# 01.net
KiCad netlist of a schematic drawn in EasyEDA
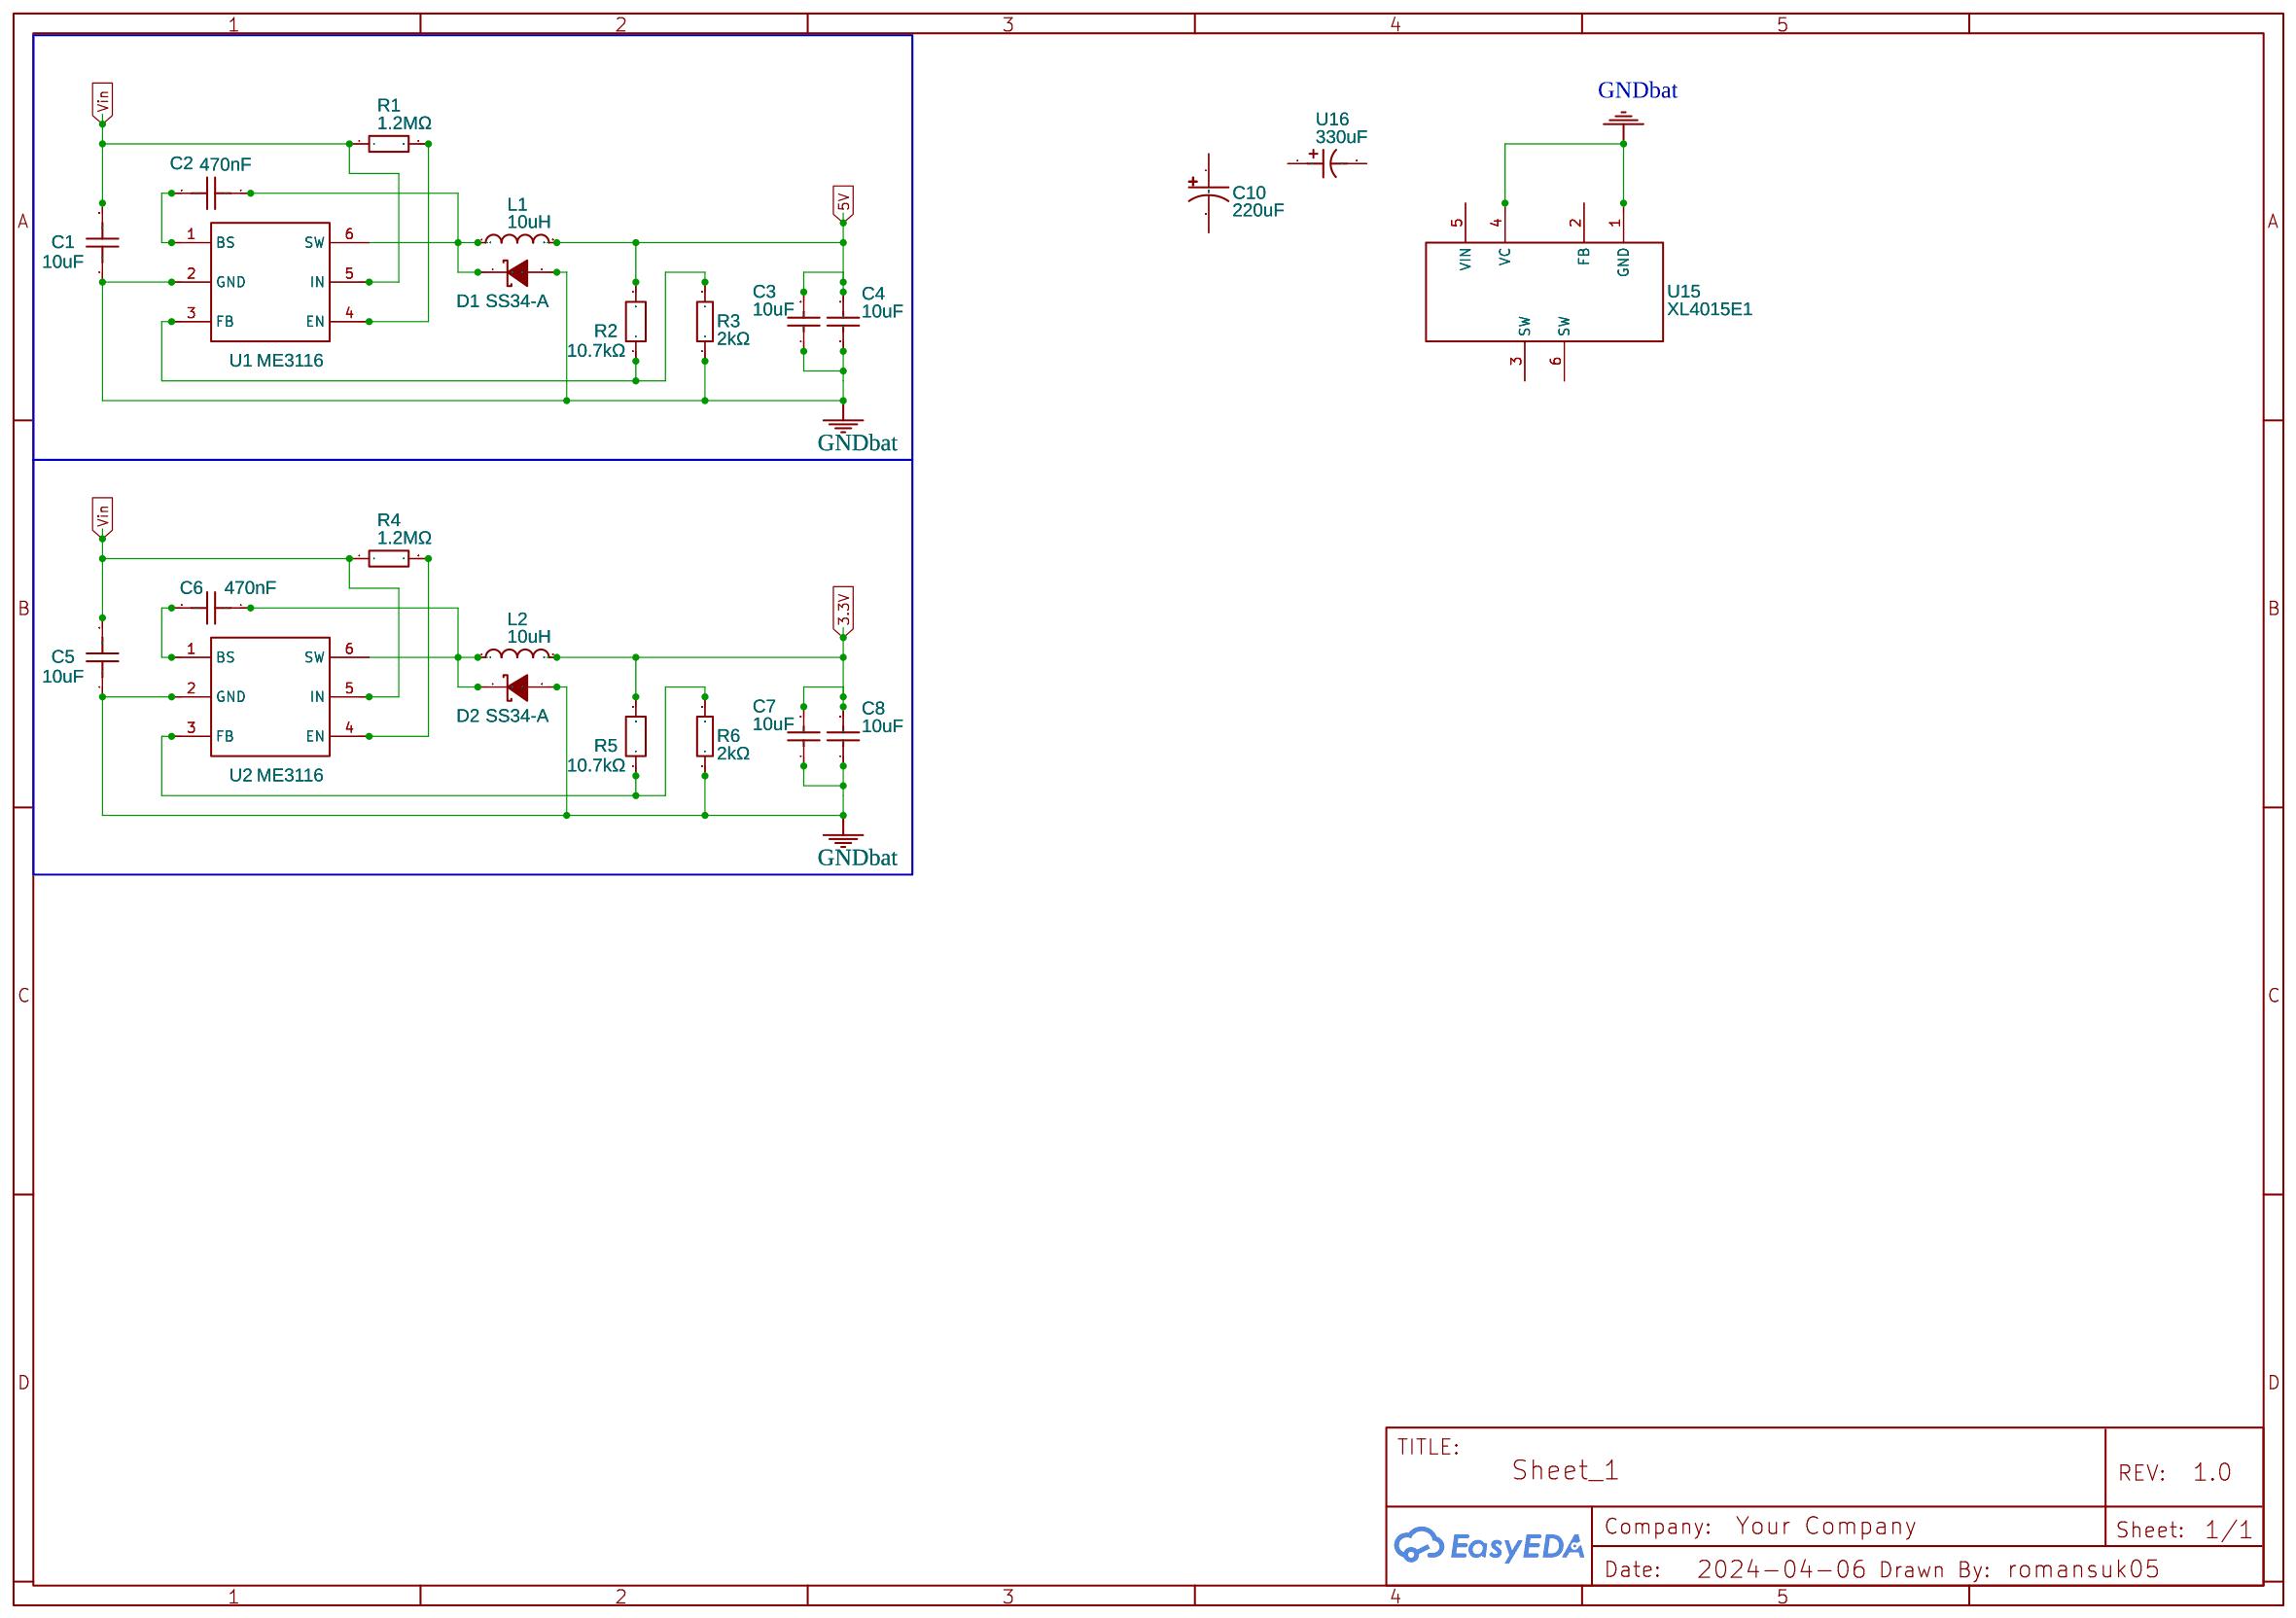
[diagram p0: schematic sheet]

(export (version "E")
  (design (tool "Eeschema 10.0.6"))
  (components
    (comp (ref "C1")
      (value "10uF")
      (fields
        (field (name "Manufacturer Part") "TCC1206X7R106K250HT")
        (field (name "Manufacturer") "CCTC(三环)")
      )
      (libsource (lib "") (part "TCC1206X7R106K250HT"))
    )
    (comp (ref "C2")
      (value "470nF")
      (fields
        (field (name "Manufacturer Part") "TCC1206X7R474K500FT")
        (field (name "Manufacturer") "CCTC(三环)")
      )
      (libsource (lib "") (part "TCC1206X7R474K500FT"))
    )
    (comp (ref "C3")
      (value "10uF")
      (fields
        (field (name "Manufacturer Part") "TMK316B7106KL-TD")
        (field (name "Manufacturer") "TAIYO YUDEN(太诱)")
      )
      (libsource (lib "") (part "TMK316B7106KL-TD"))
    )
    (comp (ref "C4")
      (value "10uF")
      (fields
        (field (name "Manufacturer Part") "TMK316B7106KL-TD")
        (field (name "Manufacturer") "TAIYO YUDEN(太诱)")
      )
      (libsource (lib "") (part "TMK316B7106KL-TD"))
    )
    (comp (ref "C5")
      (value "10uF")
      (fields
        (field (name "Manufacturer Part") "TCC1206X7R106K250HT")
        (field (name "Manufacturer") "CCTC(三环)")
      )
      (libsource (lib "") (part "TCC1206X7R106K250HT"))
    )
    (comp (ref "C6")
      (value "470nF")
      (fields
        (field (name "Manufacturer Part") "TCC1206X7R474K500FT")
        (field (name "Manufacturer") "CCTC(三环)")
      )
      (libsource (lib "") (part "TCC1206X7R474K500FT"))
    )
    (comp (ref "C7")
      (value "10uF")
      (fields
        (field (name "Manufacturer Part") "TMK316B7106KL-TD")
        (field (name "Manufacturer") "TAIYO YUDEN(太诱)")
      )
      (libsource (lib "") (part "TMK316B7106KL-TD"))
    )
    (comp (ref "C8")
      (value "10uF")
      (fields
        (field (name "Manufacturer Part") "TMK316B7106KL-TD")
        (field (name "Manufacturer") "TAIYO YUDEN(太诱)")
      )
      (libsource (lib "") (part "TMK316B7106KL-TD"))
    )
    (comp (ref "C10")
      (value "220uF")
      (fields
        (field (name "Manufacturer Part") "BXJ50V220M10*10 10TP")
        (field (name "Manufacturer") "SAMYOUNG(韩国三莹)")
      )
      (libsource (lib "") (part "BXJ-50V220-10*10"))
    )
    (comp (ref "D1")
      (value "SS34-A")
      (fields (field (name "Manufacturer") "FMS(美丽微)"))
      (libsource (lib "") (part "SS34-A"))
    )
    (comp (ref "D2")
      (value "SS34-A")
      (fields (field (name "Manufacturer") "FMS(美丽微)"))
      (libsource (lib "") (part "SS34-A"))
    )
    (comp (ref "L1")
      (value "10uH")
      (fields (field (name "Manufacturer Part") "CY75SX-10UH") (field (name "Manufacturer") "SHOU HAN(首韩)"))
      (libsource (lib "") (part "CY75SX-10UH"))
    )
    (comp (ref "L2")
      (value "10uH")
      (fields (field (name "Manufacturer Part") "CY75SX-10UH") (field (name "Manufacturer") "SHOU HAN(首韩)"))
      (libsource (lib "") (part "CY75SX-10UH"))
    )
    (comp (ref "R1")
      (value "1.2MΩ")
      (fields (field (name "Manufacturer Part") "WR12W1204FTL") (field (name "Manufacturer") "Walsin(华新科)"))
      (libsource (lib "") (part "WR12W1204FTL"))
    )
    (comp (ref "R2")
      (value "10.7kΩ")
      (fields (field (name "Manufacturer Part") "RC1206FR-0710K7L") (field (name "Manufacturer") "YAGEO(国巨)"))
      (libsource (lib "") (part "RC1206FR-0710K7L"))
    )
    (comp (ref "R3")
      (value "2kΩ")
      (fields (field (name "Manufacturer Part") "RTT06202JTP") (field (name "Manufacturer") "RALEC(旺诠)"))
      (libsource (lib "") (part "RTT06202JTP"))
    )
    (comp (ref "R4")
      (value "1.2MΩ")
      (fields (field (name "Manufacturer Part") "WR12W1204FTL") (field (name "Manufacturer") "Walsin(华新科)"))
      (libsource (lib "") (part "WR12W1204FTL"))
    )
    (comp (ref "R5")
      (value "10.7kΩ")
      (fields (field (name "Manufacturer Part") "RC1206FR-0710K7L") (field (name "Manufacturer") "YAGEO(国巨)"))
      (libsource (lib "") (part "RC1206FR-0710K7L"))
    )
    (comp (ref "R6")
      (value "2kΩ")
      (fields (field (name "Manufacturer Part") "RTT06202JTP") (field (name "Manufacturer") "RALEC(旺诠)"))
      (libsource (lib "") (part "RTT06202JTP"))
    )
    (comp (ref "U1")
      (value "ME3116")
      (fields (field (name "Manufacturer Part") "ME3116AM6G") (field (name "Manufacturer") "MICRONE(南京微盟)"))
      (libsource (lib "") (part "ME3116"))
    )
    (comp (ref "U2")
      (value "ME3116")
      (fields (field (name "Manufacturer Part") "ME3116AM6G") (field (name "Manufacturer") "MICRONE(南京微盟)"))
      (libsource (lib "") (part "ME3116"))
    )
    (comp (ref "U15")
      (value "XL4015E1")
      (fields (field (name "Manufacturer") "XLSEMI(芯龙)"))
      (libsource (lib "") (part "XL4015E1"))
    )
    (comp (ref "U16")
      (value "330uF")
      (fields (field (name "Manufacturer Part") "189RV0016") (field (name "Manufacturer") "KNSCHA(科尼盛)"))
      (libsource (lib "") (part "189RV0016"))
    )
  )
  (nets
    (net (code "1") (name "3.3V") (class "Default")
      (node (ref "C7") (pin "2") (pinfunction "2_2") (pintype "input"))
      (node (ref "C8") (pin "2") (pinfunction "2_2") (pintype "input"))
      (node (ref "L2") (pin "2") (pinfunction "2_2") (pintype "unspecified"))
      (node (ref "R5") (pin "2") (pinfunction "2_2") (pintype "unspecified"))
    )
    (net (code "2") (name "5V") (class "Default")
      (node (ref "C3") (pin "2") (pinfunction "2_2") (pintype "input"))
      (node (ref "C4") (pin "2") (pinfunction "2_2") (pintype "input"))
      (node (ref "L1") (pin "2") (pinfunction "2_2") (pintype "unspecified"))
      (node (ref "R2") (pin "2") (pinfunction "2_2") (pintype "unspecified"))
    )
    (net (code "3") (name "GNDbat") (class "Default")
      (node (ref "C1") (pin "1") (pinfunction "1_1") (pintype "unspecified"))
      (node (ref "C3") (pin "1") (pinfunction "1_1") (pintype "input"))
      (node (ref "C4") (pin "1") (pinfunction "1_1") (pintype "input"))
      (node (ref "C5") (pin "1") (pinfunction "1_1") (pintype "unspecified"))
      (node (ref "C7") (pin "1") (pinfunction "1_1") (pintype "input"))
      (node (ref "C8") (pin "1") (pinfunction "1_1") (pintype "input"))
      (node (ref "D1") (pin "2") (pinfunction "A_2") (pintype "unspecified"))
      (node (ref "D2") (pin "2") (pinfunction "A_2") (pintype "unspecified"))
      (node (ref "R3") (pin "1") (pinfunction "1_1") (pintype "input"))
      (node (ref "R6") (pin "1") (pinfunction "1_1") (pintype "input"))
      (node (ref "U1") (pin "2") (pinfunction "GND_2") (pintype "unspecified"))
      (node (ref "U15") (pin "1") (pinfunction "GND_1") (pintype "unspecified"))
      (node (ref "U15") (pin "4") (pinfunction "VC_4") (pintype "unspecified"))
      (node (ref "U2") (pin "2") (pinfunction "GND_2") (pintype "unspecified"))
    )
    (net (code "4") (name "Net-(D1-C)") (class "Default")
      (node (ref "C2") (pin "1") (pinfunction "1_1") (pintype "unspecified"))
      (node (ref "D1") (pin "1") (pinfunction "C_1") (pintype "unspecified"))
      (node (ref "L1") (pin "1") (pinfunction "1_1") (pintype "unspecified"))
      (node (ref "U1") (pin "6") (pinfunction "SW_6") (pintype "unspecified"))
    )
    (net (code "5") (name "Net-(D2-C)") (class "Default")
      (node (ref "C6") (pin "1") (pinfunction "1_1") (pintype "unspecified"))
      (node (ref "D2") (pin "1") (pinfunction "C_1") (pintype "unspecified"))
      (node (ref "L2") (pin "1") (pinfunction "1_1") (pintype "unspecified"))
      (node (ref "U2") (pin "6") (pinfunction "SW_6") (pintype "unspecified"))
    )
    (net (code "6") (name "Net-(U1-BS)") (class "Default")
      (node (ref "C2") (pin "2") (pinfunction "2_2") (pintype "unspecified"))
      (node (ref "U1") (pin "1") (pinfunction "BS_1") (pintype "unspecified"))
    )
    (net (code "7") (name "Net-(U1-EN)") (class "Default")
      (node (ref "R1") (pin "2") (pinfunction "2_2") (pintype "unspecified"))
      (node (ref "U1") (pin "4") (pinfunction "EN_4") (pintype "unspecified"))
    )
    (net (code "8") (name "Net-(U1-FB)") (class "Default")
      (node (ref "R2") (pin "1") (pinfunction "1_1") (pintype "unspecified"))
      (node (ref "R3") (pin "2") (pinfunction "2_2") (pintype "input"))
      (node (ref "U1") (pin "3") (pinfunction "FB_3") (pintype "unspecified"))
    )
    (net (code "9") (name "Net-(U2-BS)") (class "Default")
      (node (ref "C6") (pin "2") (pinfunction "2_2") (pintype "unspecified"))
      (node (ref "U2") (pin "1") (pinfunction "BS_1") (pintype "unspecified"))
    )
    (net (code "10") (name "Net-(U2-EN)") (class "Default")
      (node (ref "R4") (pin "2") (pinfunction "2_2") (pintype "unspecified"))
      (node (ref "U2") (pin "4") (pinfunction "EN_4") (pintype "unspecified"))
    )
    (net (code "11") (name "Net-(U2-FB)") (class "Default")
      (node (ref "R5") (pin "1") (pinfunction "1_1") (pintype "unspecified"))
      (node (ref "R6") (pin "2") (pinfunction "2_2") (pintype "input"))
      (node (ref "U2") (pin "3") (pinfunction "FB_3") (pintype "unspecified"))
    )
    (net (code "12") (name "Vin") (class "Default")
      (node (ref "C1") (pin "2") (pinfunction "2_2") (pintype "unspecified"))
      (node (ref "C5") (pin "2") (pinfunction "2_2") (pintype "unspecified"))
      (node (ref "R1") (pin "1") (pinfunction "1_1") (pintype "unspecified"))
      (node (ref "R4") (pin "1") (pinfunction "1_1") (pintype "unspecified"))
      (node (ref "U1") (pin "5") (pinfunction "IN_5") (pintype "unspecified"))
      (node (ref "U2") (pin "5") (pinfunction "IN_5") (pintype "unspecified"))
    )
    (net (code "13") (name "unconnected-(C10-Pad1)") (class "Default")
      (node (ref "C10") (pin "1") (pinfunction "1_1") (pintype "unspecified"))
    )
    (net (code "14") (name "unconnected-(C10-Pad2)") (class "Default")
      (node (ref "C10") (pin "2") (pinfunction "2_2") (pintype "unspecified"))
    )
    (net (code "15") (name "unconnected-(U15-FB-Pad2)") (class "Default")
      (node (ref "U15") (pin "2") (pinfunction "FB_2") (pintype "unspecified"))
    )
    (net (code "16") (name "unconnected-(U15-SW-Pad3)") (class "Default")
      (node (ref "U15") (pin "3") (pinfunction "SW_3") (pintype "unspecified"))
    )
    (net (code "17") (name "unconnected-(U15-SW-Pad6)") (class "Default")
      (node (ref "U15") (pin "6") (pinfunction "SW_6") (pintype "unspecified"))
    )
    (net (code "18") (name "unconnected-(U15-VIN-Pad5)") (class "Default")
      (node (ref "U15") (pin "5") (pinfunction "VIN_5") (pintype "unspecified"))
    )
    (net (code "19") (name "unconnected-(U16-Pad1)") (class "Default")
      (node (ref "U16") (pin "1") (pinfunction "1_1") (pintype "input"))
    )
    (net (code "20") (name "unconnected-(U16-Pad2)") (class "Default")
      (node (ref "U16") (pin "2") (pinfunction "2_2") (pintype "input"))
    )
  )
)
